# SC.net
KiCad netlist of a schematic drawn in Altium Designer
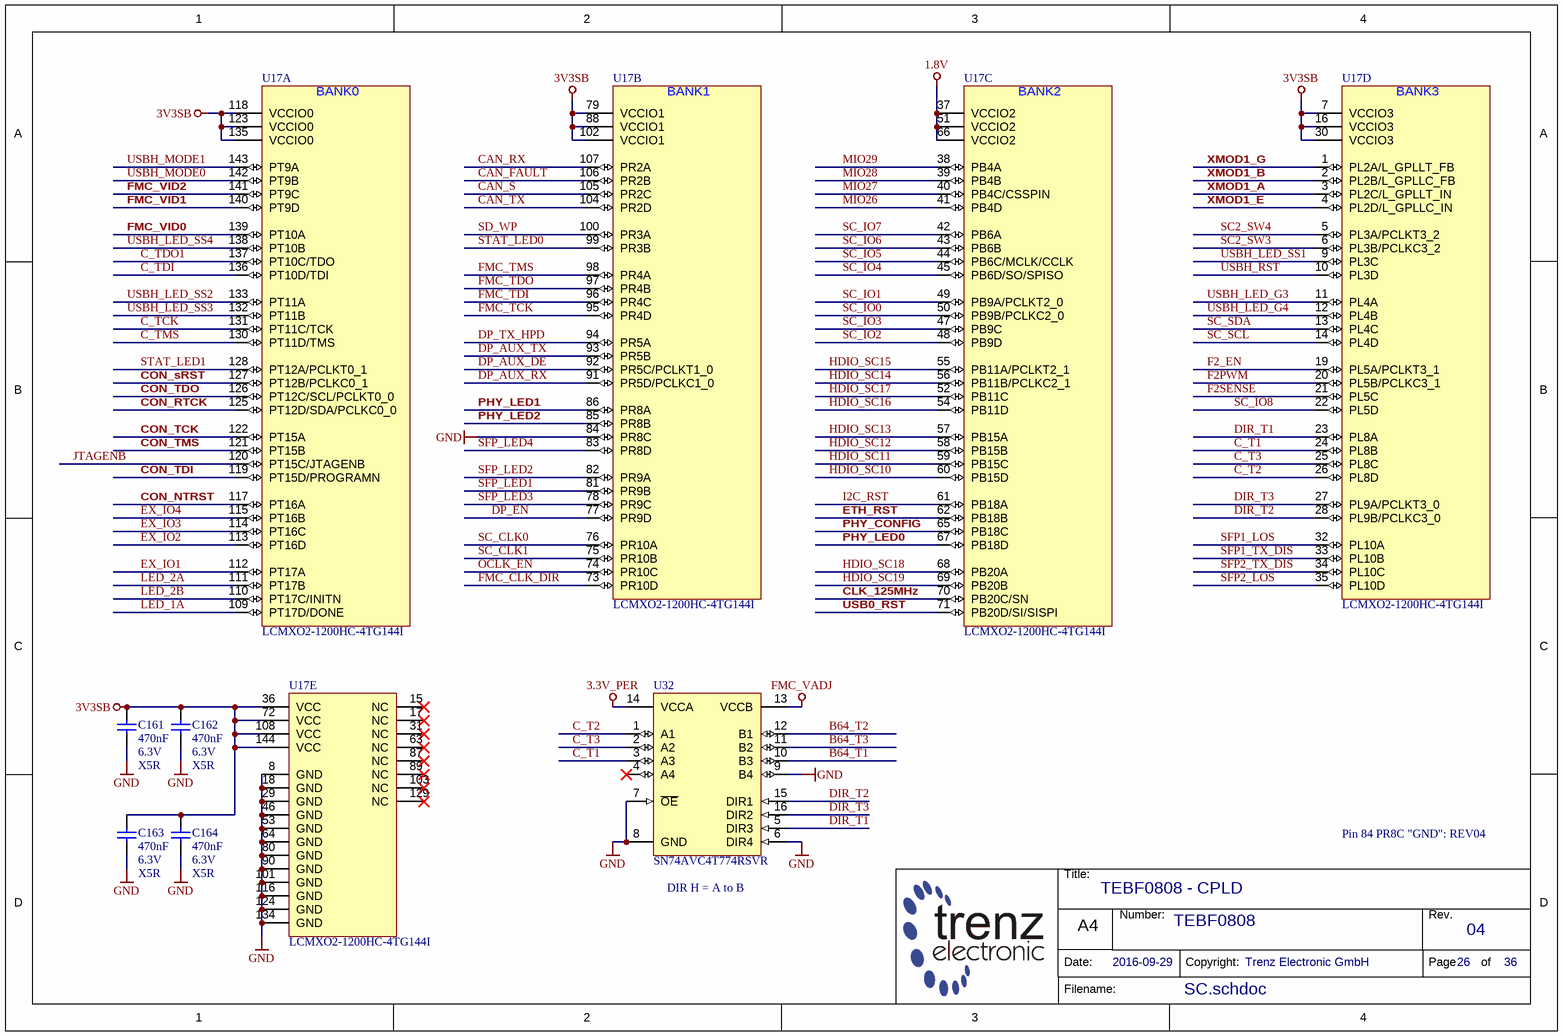
[diagram p0: SC.schdoc]

(export (version "E")
  (design (tool "Eeschema 10.0.6"))
  (components
    (comp (ref "C161")
      (value "470nF")
      (footprint "CAPC1005X55N")
      (description "KON 470nF 6,3V X5R SMD")
      (fields (field (name "VOLTAGE") "6.3V") (field (name "TECHNOLOGY") "X5R"))
      (libsource (lib "TE") (part "CAP-NP"))
    )
    (comp (ref "C162")
      (value "470nF")
      (footprint "CAPC1005X55N")
      (description "KON 470nF 6,3V X5R SMD")
      (fields (field (name "VOLTAGE") "6.3V") (field (name "TECHNOLOGY") "X5R"))
      (libsource (lib "TE") (part "CAP-NP"))
    )
    (comp (ref "C163")
      (value "470nF")
      (footprint "CAPC1005X55N")
      (description "KON 470nF 6,3V X5R SMD")
      (fields (field (name "VOLTAGE") "6.3V") (field (name "TECHNOLOGY") "X5R"))
      (libsource (lib "TE") (part "CAP-NP"))
    )
    (comp (ref "C164")
      (value "470nF")
      (footprint "CAPC1005X55N")
      (description "KON 470nF 6,3V X5R SMD")
      (fields (field (name "VOLTAGE") "6.3V") (field (name "TECHNOLOGY") "X5R"))
      (libsource (lib "TE") (part "CAP-NP"))
    )
    (comp (ref "U17")
      (value "LCMXO2-1200HC-4TG144I")
      (footprint "QFP50P2200X2200X160-144N")
      (libsource (lib "TE") (part "LCMXO2-1200HC-4TG144"))
    )
    (comp (ref "U32")
      (value "SN74AVC4T774RSVR")
      (footprint "QFN40P260X180X55-16N")
      (libsource (lib "TE") (part "SN74AVC4T774RSVR"))
    )
  )
  (nets
    (net (code "1") (name "/B64_T1") (class "Default")
      (node (ref "U32") (pin "10") (pinfunction "B3_10") (pintype "bidirectional"))
    )
    (net (code "2") (name "/B64_T2") (class "Default")
      (node (ref "U32") (pin "12") (pinfunction "B1_12") (pintype "bidirectional"))
    )
    (net (code "3") (name "/B64_T3") (class "Default")
      (node (ref "U32") (pin "11") (pinfunction "B2_11") (pintype "bidirectional"))
    )
    (net (code "4") (name "/CAN_FAULT") (class "Default")
      (node (ref "U17") (pin "106") (pinfunction "PR2B_106") (pintype "bidirectional"))
    )
    (net (code "5") (name "/CAN_RX") (class "Default")
      (node (ref "U17") (pin "107") (pinfunction "PR2A_107") (pintype "bidirectional"))
    )
    (net (code "6") (name "/CAN_S") (class "Default")
      (node (ref "U17") (pin "105") (pinfunction "PR2C_105") (pintype "bidirectional"))
    )
    (net (code "7") (name "/CAN_TX") (class "Default")
      (node (ref "U17") (pin "104") (pinfunction "PR2D_104") (pintype "bidirectional"))
    )
    (net (code "8") (name "/CLK_125MHz") (class "Default")
      (node (ref "U17") (pin "70") (pinfunction "PB20C/SN_70") (pintype "bidirectional"))
    )
    (net (code "9") (name "/CON_NTRST") (class "Default")
      (node (ref "U17") (pin "117") (pinfunction "PT16A_117") (pintype "bidirectional"))
    )
    (net (code "10") (name "/CON_RTCK") (class "Default")
      (node (ref "U17") (pin "125") (pinfunction "PT12D/SDA/PCLKC0_0_125") (pintype "bidirectional"))
    )
    (net (code "11") (name "/CON_TCK") (class "Default")
      (node (ref "U17") (pin "122") (pinfunction "PT15A_122") (pintype "bidirectional"))
    )
    (net (code "12") (name "/CON_TDI") (class "Default")
      (node (ref "U17") (pin "119") (pinfunction "PT15D/PROGRAMN_119") (pintype "bidirectional"))
    )
    (net (code "13") (name "/CON_TDO") (class "Default")
      (node (ref "U17") (pin "126") (pinfunction "PT12C/SCL/PCLKT0_0_126") (pintype "bidirectional"))
    )
    (net (code "14") (name "/CON_TMS") (class "Default")
      (node (ref "U17") (pin "121") (pinfunction "PT15B_121") (pintype "bidirectional"))
    )
    (net (code "15") (name "/CON_sRST") (class "Default")
      (node (ref "U17") (pin "127") (pinfunction "PT12B/PCLKC0_1_127") (pintype "bidirectional"))
    )
    (net (code "16") (name "/C_T1") (class "Default")
      (node (ref "U17") (pin "24") (pinfunction "PL8B_24") (pintype "bidirectional"))
      (node (ref "U32") (pin "3") (pinfunction "A3_3") (pintype "bidirectional"))
    )
    (net (code "17") (name "/C_T2") (class "Default")
      (node (ref "U17") (pin "26") (pinfunction "PL8D_26") (pintype "bidirectional"))
      (node (ref "U32") (pin "1") (pinfunction "A1_1") (pintype "bidirectional"))
    )
    (net (code "18") (name "/C_T3") (class "Default")
      (node (ref "U17") (pin "25") (pinfunction "PL8C_25") (pintype "bidirectional"))
      (node (ref "U32") (pin "2") (pinfunction "A2_2") (pintype "bidirectional"))
    )
    (net (code "19") (name "/C_TCK") (class "Default")
      (node (ref "U17") (pin "131") (pinfunction "PT11C/TCK_131") (pintype "bidirectional"))
    )
    (net (code "20") (name "/C_TDI") (class "Default")
      (node (ref "U17") (pin "136") (pinfunction "PT10D/TDI_136") (pintype "bidirectional"))
    )
    (net (code "21") (name "/C_TDO1") (class "Default")
      (node (ref "U17") (pin "137") (pinfunction "PT10C/TDO_137") (pintype "bidirectional"))
    )
    (net (code "22") (name "/C_TMS") (class "Default")
      (node (ref "U17") (pin "130") (pinfunction "PT11D/TMS_130") (pintype "bidirectional"))
    )
    (net (code "23") (name "/DIR_T1") (class "Default")
      (node (ref "U17") (pin "23") (pinfunction "PL8A_23") (pintype "bidirectional"))
      (node (ref "U32") (pin "5") (pinfunction "DIR3_5") (pintype "input"))
    )
    (net (code "24") (name "/DIR_T2") (class "Default")
      (node (ref "U17") (pin "28") (pinfunction "PL9B/PCLKC3_0_28") (pintype "bidirectional"))
      (node (ref "U32") (pin "15") (pinfunction "DIR1_15") (pintype "input"))
    )
    (net (code "25") (name "/DIR_T3") (class "Default")
      (node (ref "U17") (pin "27") (pinfunction "PL9A/PCLKT3_0_27") (pintype "bidirectional"))
      (node (ref "U32") (pin "16") (pinfunction "DIR2_16") (pintype "input"))
    )
    (net (code "26") (name "/DP_AUX_DE") (class "Default")
      (node (ref "U17") (pin "92") (pinfunction "PR5C/PCLKT1_0_92") (pintype "bidirectional"))
    )
    (net (code "27") (name "/DP_AUX_RX") (class "Default")
      (node (ref "U17") (pin "91") (pinfunction "PR5D/PCLKC1_0_91") (pintype "bidirectional"))
    )
    (net (code "28") (name "/DP_AUX_TX") (class "Default")
      (node (ref "U17") (pin "93") (pinfunction "PR5B_93") (pintype "bidirectional"))
    )
    (net (code "29") (name "/DP_EN") (class "Default")
      (node (ref "U17") (pin "77") (pinfunction "PR9D_77") (pintype "bidirectional"))
    )
    (net (code "30") (name "/DP_TX_HPD") (class "Default")
      (node (ref "U17") (pin "94") (pinfunction "PR5A_94") (pintype "bidirectional"))
    )
    (net (code "31") (name "/ETH_RST") (class "Default")
      (node (ref "U17") (pin "62") (pinfunction "PB18B_62") (pintype "bidirectional"))
    )
    (net (code "32") (name "/EX_IO1") (class "Default")
      (node (ref "U17") (pin "112") (pinfunction "PT17A_112") (pintype "bidirectional"))
    )
    (net (code "33") (name "/EX_IO2") (class "Default")
      (node (ref "U17") (pin "113") (pinfunction "PT16D_113") (pintype "bidirectional"))
    )
    (net (code "34") (name "/EX_IO3") (class "Default")
      (node (ref "U17") (pin "114") (pinfunction "PT16C_114") (pintype "bidirectional"))
    )
    (net (code "35") (name "/EX_IO4") (class "Default")
      (node (ref "U17") (pin "115") (pinfunction "PT16B_115") (pintype "bidirectional"))
    )
    (net (code "36") (name "/F2PWM") (class "Default")
      (node (ref "U17") (pin "20") (pinfunction "PL5B/PCLKC3_1_20") (pintype "bidirectional"))
    )
    (net (code "37") (name "/F2SENSE") (class "Default")
      (node (ref "U17") (pin "21") (pinfunction "PL5C_21") (pintype "bidirectional"))
    )
    (net (code "38") (name "/F2_EN") (class "Default")
      (node (ref "U17") (pin "19") (pinfunction "PL5A/PCLKT3_1_19") (pintype "bidirectional"))
    )
    (net (code "39") (name "/FMC_CLK_DIR") (class "Default")
      (node (ref "U17") (pin "73") (pinfunction "PR10D_73") (pintype "bidirectional"))
    )
    (net (code "40") (name "/FMC_TCK") (class "Default")
      (node (ref "U17") (pin "95") (pinfunction "PR4D_95") (pintype "bidirectional"))
    )
    (net (code "41") (name "/FMC_TDI") (class "Default")
      (node (ref "U17") (pin "96") (pinfunction "PR4C_96") (pintype "bidirectional"))
    )
    (net (code "42") (name "/FMC_TDO") (class "Default")
      (node (ref "U17") (pin "97") (pinfunction "PR4B_97") (pintype "bidirectional"))
    )
    (net (code "43") (name "/FMC_TMS") (class "Default")
      (node (ref "U17") (pin "98") (pinfunction "PR4A_98") (pintype "bidirectional"))
    )
    (net (code "44") (name "/FMC_VID0") (class "Default")
      (node (ref "U17") (pin "139") (pinfunction "PT10A_139") (pintype "bidirectional"))
    )
    (net (code "45") (name "/FMC_VID1") (class "Default")
      (node (ref "U17") (pin "140") (pinfunction "PT9D_140") (pintype "bidirectional"))
    )
    (net (code "46") (name "/FMC_VID2") (class "Default")
      (node (ref "U17") (pin "141") (pinfunction "PT9C_141") (pintype "bidirectional"))
    )
    (net (code "47") (name "/HDIO_SC10") (class "Default")
      (node (ref "U17") (pin "60") (pinfunction "PB15D_60") (pintype "bidirectional"))
    )
    (net (code "48") (name "/HDIO_SC11") (class "Default")
      (node (ref "U17") (pin "59") (pinfunction "PB15C_59") (pintype "bidirectional"))
    )
    (net (code "49") (name "/HDIO_SC12") (class "Default")
      (node (ref "U17") (pin "58") (pinfunction "PB15B_58") (pintype "bidirectional"))
    )
    (net (code "50") (name "/HDIO_SC13") (class "Default")
      (node (ref "U17") (pin "57") (pinfunction "PB15A_57") (pintype "bidirectional"))
    )
    (net (code "51") (name "/HDIO_SC14") (class "Default")
      (node (ref "U17") (pin "56") (pinfunction "PB11B/PCLKC2_1_56") (pintype "bidirectional"))
    )
    (net (code "52") (name "/HDIO_SC15") (class "Default")
      (node (ref "U17") (pin "55") (pinfunction "PB11A/PCLKT2_1_55") (pintype "bidirectional"))
    )
    (net (code "53") (name "/HDIO_SC16") (class "Default")
      (node (ref "U17") (pin "54") (pinfunction "PB11D_54") (pintype "bidirectional"))
    )
    (net (code "54") (name "/HDIO_SC17") (class "Default")
      (node (ref "U17") (pin "52") (pinfunction "PB11C_52") (pintype "bidirectional"))
    )
    (net (code "55") (name "/HDIO_SC18") (class "Default")
      (node (ref "U17") (pin "68") (pinfunction "PB20A_68") (pintype "bidirectional"))
    )
    (net (code "56") (name "/HDIO_SC19") (class "Default")
      (node (ref "U17") (pin "69") (pinfunction "PB20B_69") (pintype "bidirectional"))
    )
    (net (code "57") (name "/I2C_RST") (class "Default")
      (node (ref "U17") (pin "61") (pinfunction "PB18A_61") (pintype "bidirectional"))
    )
    (net (code "58") (name "/JTAGENB") (class "Default")
      (node (ref "U17") (pin "120") (pinfunction "PT15C/JTAGENB_120") (pintype "bidirectional"))
    )
    (net (code "59") (name "/LED_1A") (class "Default")
      (node (ref "U17") (pin "109") (pinfunction "PT17D/DONE_109") (pintype "bidirectional"))
    )
    (net (code "60") (name "/LED_2A") (class "Default")
      (node (ref "U17") (pin "111") (pinfunction "PT17B_111") (pintype "bidirectional"))
    )
    (net (code "61") (name "/LED_2B") (class "Default")
      (node (ref "U17") (pin "110") (pinfunction "PT17C/INITN_110") (pintype "bidirectional"))
    )
    (net (code "62") (name "/MIO26") (class "Default")
      (node (ref "U17") (pin "41") (pinfunction "PB4D_41") (pintype "bidirectional"))
    )
    (net (code "63") (name "/MIO27") (class "Default")
      (node (ref "U17") (pin "40") (pinfunction "PB4C/CSSPIN_40") (pintype "bidirectional"))
    )
    (net (code "64") (name "/MIO28") (class "Default")
      (node (ref "U17") (pin "39") (pinfunction "PB4B_39") (pintype "bidirectional"))
    )
    (net (code "65") (name "/MIO29") (class "Default")
      (node (ref "U17") (pin "38") (pinfunction "PB4A_38") (pintype "bidirectional"))
    )
    (net (code "66") (name "/OCLK_EN") (class "Default")
      (node (ref "U17") (pin "74") (pinfunction "PR10C_74") (pintype "bidirectional"))
    )
    (net (code "67") (name "/PHY_CONFIG") (class "Default")
      (node (ref "U17") (pin "65") (pinfunction "PB18C_65") (pintype "bidirectional"))
    )
    (net (code "68") (name "/PHY_LED0") (class "Default")
      (node (ref "U17") (pin "67") (pinfunction "PB18D_67") (pintype "bidirectional"))
    )
    (net (code "69") (name "/PHY_LED1") (class "Default")
      (node (ref "U17") (pin "86") (pinfunction "PR8A_86") (pintype "bidirectional"))
    )
    (net (code "70") (name "/PHY_LED2") (class "Default")
      (node (ref "U17") (pin "85") (pinfunction "PR8B_85") (pintype "bidirectional"))
    )
    (net (code "71") (name "/SC2_SW3") (class "Default")
      (node (ref "U17") (pin "6") (pinfunction "PL3B/PCLKC3_2_6") (pintype "bidirectional"))
    )
    (net (code "72") (name "/SC2_SW4") (class "Default")
      (node (ref "U17") (pin "5") (pinfunction "PL3A/PCLKT3_2_5") (pintype "bidirectional"))
    )
    (net (code "73") (name "/SC_CLK0") (class "Default")
      (node (ref "U17") (pin "76") (pinfunction "PR10A_76") (pintype "bidirectional"))
    )
    (net (code "74") (name "/SC_CLK1") (class "Default")
      (node (ref "U17") (pin "75") (pinfunction "PR10B_75") (pintype "bidirectional"))
    )
    (net (code "75") (name "/SC_IO0") (class "Default")
      (node (ref "U17") (pin "50") (pinfunction "PB9B/PCLKC2_0_50") (pintype "bidirectional"))
    )
    (net (code "76") (name "/SC_IO1") (class "Default")
      (node (ref "U17") (pin "49") (pinfunction "PB9A/PCLKT2_0_49") (pintype "bidirectional"))
    )
    (net (code "77") (name "/SC_IO2") (class "Default")
      (node (ref "U17") (pin "48") (pinfunction "PB9D_48") (pintype "bidirectional"))
    )
    (net (code "78") (name "/SC_IO3") (class "Default")
      (node (ref "U17") (pin "47") (pinfunction "PB9C_47") (pintype "bidirectional"))
    )
    (net (code "79") (name "/SC_IO4") (class "Default")
      (node (ref "U17") (pin "45") (pinfunction "PB6D/SO/SPISO_45") (pintype "bidirectional"))
    )
    (net (code "80") (name "/SC_IO5") (class "Default")
      (node (ref "U17") (pin "44") (pinfunction "PB6C/MCLK/CCLK_44") (pintype "bidirectional"))
    )
    (net (code "81") (name "/SC_IO6") (class "Default")
      (node (ref "U17") (pin "43") (pinfunction "PB6B_43") (pintype "bidirectional"))
    )
    (net (code "82") (name "/SC_IO7") (class "Default")
      (node (ref "U17") (pin "42") (pinfunction "PB6A_42") (pintype "bidirectional"))
    )
    (net (code "83") (name "/SC_IO8") (class "Default")
      (node (ref "U17") (pin "22") (pinfunction "PL5D_22") (pintype "bidirectional"))
    )
    (net (code "84") (name "/SC_SCL") (class "Default")
      (node (ref "U17") (pin "14") (pinfunction "PL4D_14") (pintype "bidirectional"))
    )
    (net (code "85") (name "/SC_SDA") (class "Default")
      (node (ref "U17") (pin "13") (pinfunction "PL4C_13") (pintype "bidirectional"))
    )
    (net (code "86") (name "/SD_WP") (class "Default")
      (node (ref "U17") (pin "100") (pinfunction "PR3A_100") (pintype "bidirectional"))
    )
    (net (code "87") (name "/SFP1_LOS") (class "Default")
      (node (ref "U17") (pin "32") (pinfunction "PL10A_32") (pintype "bidirectional"))
    )
    (net (code "88") (name "/SFP1_TX_DIS") (class "Default")
      (node (ref "U17") (pin "33") (pinfunction "PL10B_33") (pintype "bidirectional"))
    )
    (net (code "89") (name "/SFP2_LOS") (class "Default")
      (node (ref "U17") (pin "35") (pinfunction "PL10D_35") (pintype "bidirectional"))
    )
    (net (code "90") (name "/SFP2_TX_DIS") (class "Default")
      (node (ref "U17") (pin "34") (pinfunction "PL10C_34") (pintype "bidirectional"))
    )
    (net (code "91") (name "/SFP_LED1") (class "Default")
      (node (ref "U17") (pin "81") (pinfunction "PR9B_81") (pintype "bidirectional"))
    )
    (net (code "92") (name "/SFP_LED2") (class "Default")
      (node (ref "U17") (pin "82") (pinfunction "PR9A_82") (pintype "bidirectional"))
    )
    (net (code "93") (name "/SFP_LED3") (class "Default")
      (node (ref "U17") (pin "78") (pinfunction "PR9C_78") (pintype "bidirectional"))
    )
    (net (code "94") (name "/SFP_LED4") (class "Default")
      (node (ref "U17") (pin "83") (pinfunction "PR8D_83") (pintype "bidirectional"))
    )
    (net (code "95") (name "/STAT_LED0") (class "Default")
      (node (ref "U17") (pin "99") (pinfunction "PR3B_99") (pintype "bidirectional"))
    )
    (net (code "96") (name "/STAT_LED1") (class "Default")
      (node (ref "U17") (pin "128") (pinfunction "PT12A/PCLKT0_1_128") (pintype "bidirectional"))
    )
    (net (code "97") (name "/USB0_RST") (class "Default")
      (node (ref "U17") (pin "71") (pinfunction "PB20D/SI/SISPI_71") (pintype "bidirectional"))
    )
    (net (code "98") (name "/USBH_LED_G3") (class "Default")
      (node (ref "U17") (pin "11") (pinfunction "PL4A_11") (pintype "bidirectional"))
    )
    (net (code "99") (name "/USBH_LED_G4") (class "Default")
      (node (ref "U17") (pin "12") (pinfunction "PL4B_12") (pintype "bidirectional"))
    )
    (net (code "100") (name "/USBH_LED_SS1") (class "Default")
      (node (ref "U17") (pin "9") (pinfunction "PL3C_9") (pintype "bidirectional"))
    )
    (net (code "101") (name "/USBH_LED_SS2") (class "Default")
      (node (ref "U17") (pin "133") (pinfunction "PT11A_133") (pintype "bidirectional"))
    )
    (net (code "102") (name "/USBH_LED_SS3") (class "Default")
      (node (ref "U17") (pin "132") (pinfunction "PT11B_132") (pintype "bidirectional"))
    )
    (net (code "103") (name "/USBH_LED_SS4") (class "Default")
      (node (ref "U17") (pin "138") (pinfunction "PT10B_138") (pintype "bidirectional"))
    )
    (net (code "104") (name "/USBH_MODE0") (class "Default")
      (node (ref "U17") (pin "142") (pinfunction "PT9B_142") (pintype "bidirectional"))
    )
    (net (code "105") (name "/USBH_MODE1") (class "Default")
      (node (ref "U17") (pin "143") (pinfunction "PT9A_143") (pintype "bidirectional"))
    )
    (net (code "106") (name "/USBH_RST") (class "Default")
      (node (ref "U17") (pin "10") (pinfunction "PL3D_10") (pintype "bidirectional"))
    )
    (net (code "107") (name "/XMOD1_A") (class "Default")
      (node (ref "U17") (pin "3") (pinfunction "PL2C/L_GPLLT_IN_3") (pintype "bidirectional"))
    )
    (net (code "108") (name "/XMOD1_B") (class "Default")
      (node (ref "U17") (pin "2") (pinfunction "PL2B/L_GPLLC_FB_2") (pintype "bidirectional"))
    )
    (net (code "109") (name "/XMOD1_E") (class "Default")
      (node (ref "U17") (pin "4") (pinfunction "PL2D/L_GPLLC_IN_4") (pintype "bidirectional"))
    )
    (net (code "110") (name "/XMOD1_G") (class "Default")
      (node (ref "U17") (pin "1") (pinfunction "PL2A/L_GPLLT_FB_1") (pintype "bidirectional"))
    )
    (net (code "111") (name "1.8V") (class "Default")
      (node (ref "U17") (pin "37") (pinfunction "VCCIO2_37") (pintype "power_in"))
      (node (ref "U17") (pin "51") (pinfunction "VCCIO2_51") (pintype "power_in"))
      (node (ref "U17") (pin "66") (pinfunction "VCCIO2_66") (pintype "power_in"))
    )
    (net (code "112") (name "3.3V_PER") (class "Default")
      (node (ref "U32") (pin "14") (pinfunction "VCCA_14") (pintype "power_in"))
    )
    (net (code "113") (name "3V3SB") (class "Default")
      (node (ref "C161") (pin "1") (pinfunction "1_1") (pintype "passive"))
      (node (ref "C162") (pin "1") (pinfunction "1_1") (pintype "passive"))
      (node (ref "C163") (pin "1") (pinfunction "1_1") (pintype "passive"))
      (node (ref "C164") (pin "1") (pinfunction "1_1") (pintype "passive"))
      (node (ref "U17") (pin "102") (pinfunction "VCCIO1_102") (pintype "power_in"))
      (node (ref "U17") (pin "108") (pinfunction "VCC_108") (pintype "power_in"))
      (node (ref "U17") (pin "118") (pinfunction "VCCIO0_118") (pintype "power_in"))
      (node (ref "U17") (pin "123") (pinfunction "VCCIO0_123") (pintype "power_in"))
      (node (ref "U17") (pin "135") (pinfunction "VCCIO0_135") (pintype "power_in"))
      (node (ref "U17") (pin "144") (pinfunction "VCC_144") (pintype "power_in"))
      (node (ref "U17") (pin "16") (pinfunction "VCCIO3_16") (pintype "power_in"))
      (node (ref "U17") (pin "30") (pinfunction "VCCIO3_30") (pintype "power_in"))
      (node (ref "U17") (pin "36") (pinfunction "VCC_36") (pintype "power_in"))
      (node (ref "U17") (pin "7") (pinfunction "VCCIO3_7") (pintype "power_in"))
      (node (ref "U17") (pin "72") (pinfunction "VCC_72") (pintype "power_in"))
      (node (ref "U17") (pin "79") (pinfunction "VCCIO1_79") (pintype "power_in"))
      (node (ref "U17") (pin "88") (pinfunction "VCCIO1_88") (pintype "power_in"))
    )
    (net (code "114") (name "FMC_VADJ") (class "Default")
      (node (ref "U32") (pin "13") (pinfunction "VCCB_13") (pintype "power_in"))
    )
    (net (code "115") (name "GND") (class "Default")
      (node (ref "C161") (pin "2") (pinfunction "2_2") (pintype "passive"))
      (node (ref "C162") (pin "2") (pinfunction "2_2") (pintype "passive"))
      (node (ref "C163") (pin "2") (pinfunction "2_2") (pintype "passive"))
      (node (ref "C164") (pin "2") (pinfunction "2_2") (pintype "passive"))
      (node (ref "U17") (pin "101") (pinfunction "GND_101") (pintype "power_in"))
      (node (ref "U17") (pin "116") (pinfunction "GND_116") (pintype "power_in"))
      (node (ref "U17") (pin "124") (pinfunction "GND_124") (pintype "power_in"))
      (node (ref "U17") (pin "134") (pinfunction "GND_134") (pintype "power_in"))
      (node (ref "U17") (pin "18") (pinfunction "GND_18") (pintype "power_in"))
      (node (ref "U17") (pin "29") (pinfunction "GND_29") (pintype "power_in"))
      (node (ref "U17") (pin "46") (pinfunction "GND_46") (pintype "power_in"))
      (node (ref "U17") (pin "53") (pinfunction "GND_53") (pintype "power_in"))
      (node (ref "U17") (pin "64") (pinfunction "GND_64") (pintype "power_in"))
      (node (ref "U17") (pin "8") (pinfunction "GND_8") (pintype "power_in"))
      (node (ref "U17") (pin "80") (pinfunction "GND_80") (pintype "power_in"))
      (node (ref "U17") (pin "84") (pinfunction "PR8C_84") (pintype "bidirectional"))
      (node (ref "U17") (pin "90") (pinfunction "GND_90") (pintype "power_in"))
      (node (ref "U32") (pin "6") (pinfunction "DIR4_6") (pintype "input"))
      (node (ref "U32") (pin "7") (pinfunction "~{OE}_7") (pintype "input"))
      (node (ref "U32") (pin "8") (pinfunction "GND_8") (pintype "power_in"))
      (node (ref "U32") (pin "9") (pinfunction "B4_9") (pintype "bidirectional"))
    )
    (net (code "116") (name "unconnected-(U17E-NC-Pad15)") (class "Default")
      (node (ref "U17") (pin "15") (pinfunction "NC_15") (pintype "passive+no_connect"))
    )
    (net (code "117") (name "unconnected-(U17E-NC-Pad17)") (class "Default")
      (node (ref "U17") (pin "17") (pinfunction "NC_17") (pintype "passive+no_connect"))
    )
    (net (code "118") (name "unconnected-(U17E-NC-Pad31)") (class "Default")
      (node (ref "U17") (pin "31") (pinfunction "NC_31") (pintype "passive+no_connect"))
    )
    (net (code "119") (name "unconnected-(U17E-NC-Pad63)") (class "Default")
      (node (ref "U17") (pin "63") (pinfunction "NC_63") (pintype "passive+no_connect"))
    )
    (net (code "120") (name "unconnected-(U17E-NC-Pad87)") (class "Default")
      (node (ref "U17") (pin "87") (pinfunction "NC_87") (pintype "passive+no_connect"))
    )
    (net (code "121") (name "unconnected-(U17E-NC-Pad89)") (class "Default")
      (node (ref "U17") (pin "89") (pinfunction "NC_89") (pintype "passive+no_connect"))
    )
    (net (code "122") (name "unconnected-(U17E-NC-Pad103)") (class "Default")
      (node (ref "U17") (pin "103") (pinfunction "NC_103") (pintype "passive+no_connect"))
    )
    (net (code "123") (name "unconnected-(U17E-NC-Pad129)") (class "Default")
      (node (ref "U17") (pin "129") (pinfunction "NC_129") (pintype "passive+no_connect"))
    )
    (net (code "124") (name "unconnected-(U32-A4-Pad4)") (class "Default")
      (node (ref "U32") (pin "4") (pinfunction "A4_4") (pintype "bidirectional+no_connect"))
    )
  )
)
